# node.net
KiCad netlist of a schematic drawn in EAGLE
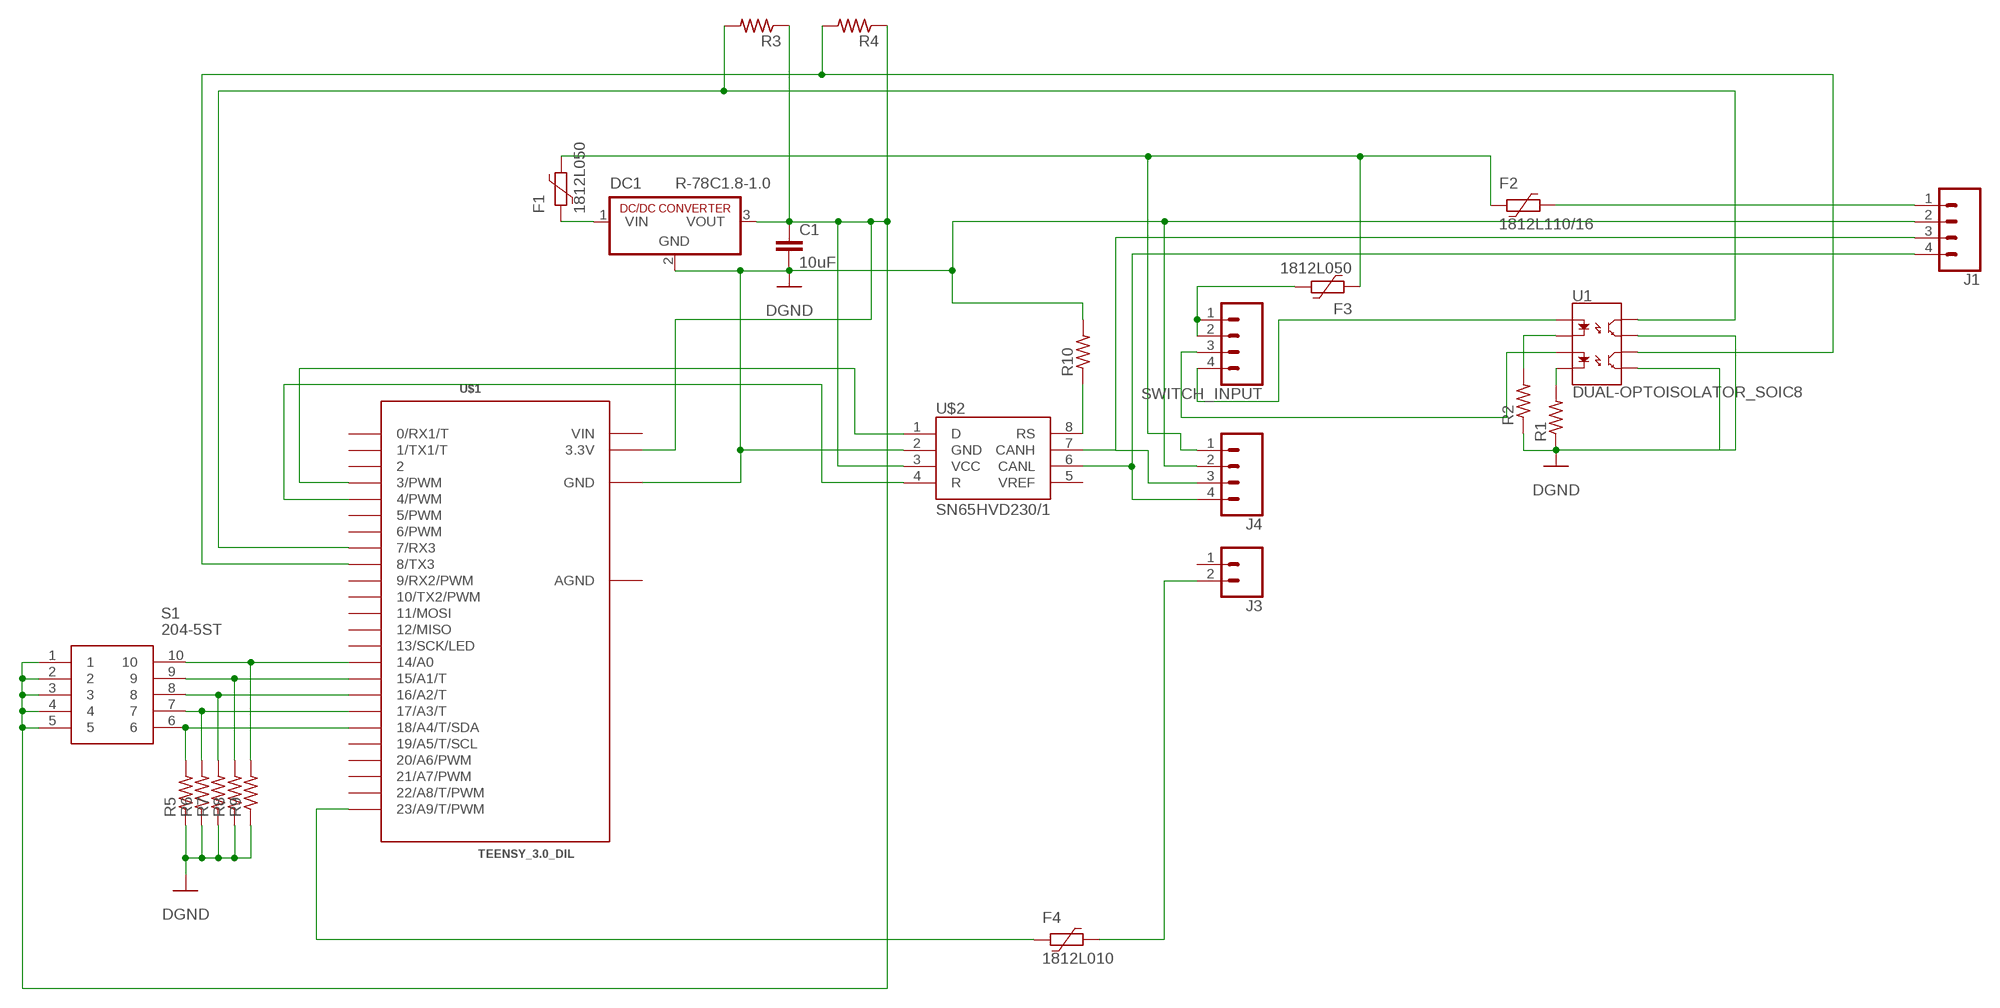
[diagram p0: schematic, sheet 1]

(export (version "E")
  (design (tool "Eeschema 10.0.6"))
  (components
    (comp (ref "C1")
      (value "10uF")
      (footprint "eagle-import:1206")
      (libsource (lib "eagle-import") (part "10UF-1206-6.3V-20%"))
    )
    (comp (ref "DC1")
      (value "R-78C1.8-1.0")
      (footprint "eagle-import:SIP3")
      (libsource (lib "eagle-import") (part "R-78C-1.01.8"))
    )
    (comp (ref "F1")
      (value "1812L050")
      (footprint "eagle-import:1812L")
      (fields (field (name "MF") "Littelfuse"))
      (libsource (lib "eagle-import") (part "?1812L050"))
    )
    (comp (ref "F2")
      (value "1812L110/16")
      (footprint "eagle-import:1812L")
      (fields (field (name "MF") "Littelfuse"))
      (libsource (lib "eagle-import") (part "?1812L110/16"))
    )
    (comp (ref "F3")
      (value "1812L050")
      (footprint "eagle-import:1812L")
      (fields (field (name "MF") "Littelfuse"))
      (libsource (lib "eagle-import") (part "?1812L050"))
    )
    (comp (ref "F4")
      (value "1812L010")
      (footprint "eagle-import:1812L")
      (fields (field (name "MF") "Littelfuse"))
      (libsource (lib "eagle-import") (part "?1812L010"))
    )
    (comp (ref "J1")
      (value "CONN_04POLAR")
      (footprint "eagle-import:MOLEX-1X4")
      (libsource (lib "eagle-import") (part "CONN_04POLAR"))
    )
    (comp (ref "J3")
      (value "CONN_02POLAR")
      (footprint "eagle-import:MOLEX-1X2")
      (libsource (lib "eagle-import") (part "CONN_02POLAR"))
    )
    (comp (ref "J4")
      (value "CONN_04POLAR")
      (footprint "eagle-import:MOLEX-1X4")
      (libsource (lib "eagle-import") (part "CONN_04POLAR"))
    )
    (comp (ref "R1")
      (value "R-US_R1206")
      (footprint "eagle-import:R1206")
      (libsource (lib "eagle-import") (part "R-US_R1206"))
    )
    (comp (ref "R2")
      (value "R-US_R1206")
      (footprint "eagle-import:R1206")
      (libsource (lib "eagle-import") (part "R-US_R1206"))
    )
    (comp (ref "R3")
      (value "R-US_R1206")
      (footprint "eagle-import:R1206")
      (libsource (lib "eagle-import") (part "R-US_R1206"))
    )
    (comp (ref "R4")
      (value "R-US_R1206")
      (footprint "eagle-import:R1206")
      (libsource (lib "eagle-import") (part "R-US_R1206"))
    )
    (comp (ref "R5")
      (value "R-US_R1206")
      (footprint "eagle-import:R1206")
      (libsource (lib "eagle-import") (part "R-US_R1206"))
    )
    (comp (ref "R6")
      (value "R-US_R1206")
      (footprint "eagle-import:R1206")
      (libsource (lib "eagle-import") (part "R-US_R1206"))
    )
    (comp (ref "R7")
      (value "R-US_R1206")
      (footprint "eagle-import:R1206")
      (libsource (lib "eagle-import") (part "R-US_R1206"))
    )
    (comp (ref "R8")
      (value "R-US_R1206")
      (footprint "eagle-import:R1206")
      (libsource (lib "eagle-import") (part "R-US_R1206"))
    )
    (comp (ref "R9")
      (value "R-US_R1206")
      (footprint "eagle-import:R1206")
      (libsource (lib "eagle-import") (part "R-US_R1206"))
    )
    (comp (ref "R10")
      (value "R-US_R1206")
      (footprint "eagle-import:R1206")
      (libsource (lib "eagle-import") (part "R-US_R1206"))
    )
    (comp (ref "S1")
      (value "204-5ST")
      (footprint "eagle-import:SOP254P1152X760-10N")
      (libsource (lib "eagle-import") (part "204-5ST"))
    )
    (comp (ref "SWITCH_INPUT")
      (value "CONN_04POLAR")
      (footprint "eagle-import:MOLEX-1X4")
      (libsource (lib "eagle-import") (part "CONN_04POLAR"))
    )
    (comp (ref "U$1")
      (value "TEENSY_3.0_DIL")
      (footprint "eagle-import:TEENSY_3.0-3.2&LC_DIL")
      (libsource (lib "eagle-import") (part "TEENSY_3.0_DIL"))
    )
    (comp (ref "U$2")
      (value "SN65HVD230/1")
      (footprint "eagle-import:SO8")
      (libsource (lib "eagle-import") (part "SN65HVD230/1"))
    )
    (comp (ref "U1")
      (value "DUAL-OPTOISOLATOR_SOIC8")
      (footprint "eagle-import:SO08")
      (libsource (lib "eagle-import") (part "DUAL-OPTOISOLATOR_SOIC8"))
    )
  )
  (nets
    (net (code "1") (name "/AGND") (class "Default")
      (node (ref "U$1") (pin "AGND") (pinfunction "AGND_AGND") (pintype "power_in"))
    )
    (net (code "2") (name "/VIN") (class "Default")
      (node (ref "U$1") (pin "VIN") (pinfunction "VIN_VIN") (pintype "power_in"))
    )
    (net (code "3") (name "DGND") (class "Default")
      (node (ref "C1") (pin "2") (pinfunction "2_2") (pintype "passive"))
      (node (ref "DC1") (pin "2") (pinfunction "GND_2") (pintype "passive"))
      (node (ref "J1") (pin "2") (pinfunction "2_2") (pintype "passive"))
      (node (ref "J4") (pin "2") (pinfunction "2_2") (pintype "passive"))
      (node (ref "R1") (pin "1") (pinfunction "1_1") (pintype "passive"))
      (node (ref "R10") (pin "2") (pinfunction "2_2") (pintype "passive"))
      (node (ref "R2") (pin "1") (pinfunction "1_1") (pintype "passive"))
      (node (ref "R5") (pin "1") (pinfunction "1_1") (pintype "passive"))
      (node (ref "R6") (pin "1") (pinfunction "1_1") (pintype "passive"))
      (node (ref "R7") (pin "1") (pinfunction "1_1") (pintype "passive"))
      (node (ref "R8") (pin "1") (pinfunction "1_1") (pintype "passive"))
      (node (ref "R9") (pin "1") (pinfunction "1_1") (pintype "passive"))
      (node (ref "U$1") (pin "GND") (pinfunction "GND_GND") (pintype "power_in"))
      (node (ref "U$2") (pin "2") (pinfunction "GND_2") (pintype "power_in"))
      (node (ref "U1") (pin "5") (pinfunction "EM2_5") (pintype "bidirectional"))
      (node (ref "U1") (pin "7") (pinfunction "EM1_7") (pintype "bidirectional"))
    )
    (net (code "4") (name "Net-(DC1-VIN)") (class "Default")
      (node (ref "DC1") (pin "1") (pinfunction "VIN_1") (pintype "passive"))
      (node (ref "F1") (pin "2") (pinfunction "2_2") (pintype "passive"))
    )
    (net (code "5") (name "Net-(DC1-VOUT)") (class "Default")
      (node (ref "C1") (pin "1") (pinfunction "1_1") (pintype "passive"))
      (node (ref "DC1") (pin "3") (pinfunction "VOUT_3") (pintype "passive"))
      (node (ref "R3") (pin "1") (pinfunction "1_1") (pintype "passive"))
      (node (ref "R4") (pin "1") (pinfunction "1_1") (pintype "passive"))
      (node (ref "S1") (pin "1") (pinfunction "1_1") (pintype "input"))
      (node (ref "S1") (pin "2") (pinfunction "2_2") (pintype "input"))
      (node (ref "S1") (pin "3") (pinfunction "3_3") (pintype "input"))
      (node (ref "S1") (pin "4") (pinfunction "4_4") (pintype "input"))
      (node (ref "S1") (pin "5") (pinfunction "5_5") (pintype "input"))
      (node (ref "U$1") (pin "3.3V") (pinfunction "3.3V_3.3V") (pintype "power_in"))
      (node (ref "U$2") (pin "3") (pinfunction "VCC_3") (pintype "power_in"))
    )
    (net (code "6") (name "Net-(F1-Pad1)") (class "Default")
      (node (ref "F1") (pin "1") (pinfunction "1_1") (pintype "passive"))
      (node (ref "F2") (pin "2") (pinfunction "2_2") (pintype "passive"))
      (node (ref "F3") (pin "2") (pinfunction "2_2") (pintype "passive"))
      (node (ref "J4") (pin "1") (pinfunction "1_1") (pintype "passive"))
    )
    (net (code "7") (name "Net-(F2-Pad1)") (class "Default")
      (node (ref "F2") (pin "1") (pinfunction "1_1") (pintype "passive"))
      (node (ref "J1") (pin "1") (pinfunction "1_1") (pintype "passive"))
    )
    (net (code "8") (name "Net-(F3-Pad1)") (class "Default")
      (node (ref "F3") (pin "1") (pinfunction "1_1") (pintype "passive"))
      (node (ref "SWITCH_INPUT") (pin "1") (pinfunction "1_1") (pintype "passive"))
      (node (ref "SWITCH_INPUT") (pin "2") (pinfunction "2_2") (pintype "passive"))
    )
    (net (code "9") (name "Net-(F4-Pad1)") (class "Default")
      (node (ref "F4") (pin "1") (pinfunction "1_1") (pintype "passive"))
      (node (ref "J3") (pin "2") (pinfunction "2_2") (pintype "passive"))
    )
    (net (code "10") (name "Net-(R9-Pad2)") (class "Default")
      (node (ref "R9") (pin "2") (pinfunction "2_2") (pintype "passive"))
      (node (ref "S1") (pin "10") (pinfunction "10_10") (pintype "output"))
      (node (ref "U$1") (pin "14/A0") (pinfunction "14/A0_14/A0") (pintype "bidirectional"))
    )
    (net (code "11") (name "Net-(U$1-3{slash}PWM)") (class "Default")
      (node (ref "U$1") (pin "3") (pinfunction "3/PWM_3") (pintype "bidirectional"))
      (node (ref "U$2") (pin "1") (pinfunction "D_1") (pintype "bidirectional"))
    )
    (net (code "12") (name "Net-(U$1-4{slash}PWM)") (class "Default")
      (node (ref "U$1") (pin "4") (pinfunction "4/PWM_4") (pintype "bidirectional"))
      (node (ref "U$2") (pin "4") (pinfunction "R_4") (pintype "bidirectional"))
    )
    (net (code "13") (name "Net-(U$1-7{slash}RX3)") (class "Default")
      (node (ref "R3") (pin "2") (pinfunction "2_2") (pintype "passive"))
      (node (ref "U$1") (pin "7") (pinfunction "7/RX3_7") (pintype "bidirectional"))
      (node (ref "U1") (pin "8") (pinfunction "CL1_8") (pintype "bidirectional"))
    )
    (net (code "14") (name "Net-(U$1-8{slash}TX3)") (class "Default")
      (node (ref "R4") (pin "2") (pinfunction "2_2") (pintype "passive"))
      (node (ref "U$1") (pin "8") (pinfunction "8/TX3_8") (pintype "bidirectional"))
      (node (ref "U1") (pin "6") (pinfunction "CL2_6") (pintype "bidirectional"))
    )
    (net (code "15") (name "Net-(U$1-15{slash}A1{slash}T)") (class "Default")
      (node (ref "R8") (pin "2") (pinfunction "2_2") (pintype "passive"))
      (node (ref "S1") (pin "9") (pinfunction "9_9") (pintype "output"))
      (node (ref "U$1") (pin "15/A1") (pinfunction "15/A1/T_15/A1") (pintype "bidirectional"))
    )
    (net (code "16") (name "Net-(U$1-16{slash}A2{slash}T)") (class "Default")
      (node (ref "R7") (pin "2") (pinfunction "2_2") (pintype "passive"))
      (node (ref "S1") (pin "8") (pinfunction "8_8") (pintype "output"))
      (node (ref "U$1") (pin "16/A2") (pinfunction "16/A2/T_16/A2") (pintype "bidirectional"))
    )
    (net (code "17") (name "Net-(U$1-17{slash}A3{slash}T)") (class "Default")
      (node (ref "R6") (pin "2") (pinfunction "2_2") (pintype "passive"))
      (node (ref "S1") (pin "7") (pinfunction "7_7") (pintype "output"))
      (node (ref "U$1") (pin "17/A3") (pinfunction "17/A3/T_17/A3") (pintype "bidirectional"))
    )
    (net (code "18") (name "Net-(U$1-18{slash}A4{slash}T{slash}SDA)") (class "Default")
      (node (ref "R5") (pin "2") (pinfunction "2_2") (pintype "passive"))
      (node (ref "S1") (pin "6") (pinfunction "6_6") (pintype "output"))
      (node (ref "U$1") (pin "18/A4") (pinfunction "18/A4/T/SDA_18/A4") (pintype "bidirectional"))
    )
    (net (code "19") (name "Net-(U$1-23{slash}A9{slash}T{slash}PWM)") (class "Default")
      (node (ref "F4") (pin "2") (pinfunction "2_2") (pintype "passive"))
      (node (ref "U$1") (pin "23/A9") (pinfunction "23/A9/T/PWM_23/A9") (pintype "bidirectional"))
    )
    (net (code "20") (name "Net-(U$2-CANH)") (class "Default")
      (node (ref "J1") (pin "3") (pinfunction "3_3") (pintype "passive"))
      (node (ref "J4") (pin "3") (pinfunction "3_3") (pintype "passive"))
      (node (ref "U$2") (pin "7") (pinfunction "CANH_7") (pintype "bidirectional"))
    )
    (net (code "21") (name "Net-(U$2-CANL)") (class "Default")
      (node (ref "J1") (pin "4") (pinfunction "4_4") (pintype "passive"))
      (node (ref "J4") (pin "4") (pinfunction "4_4") (pintype "passive"))
      (node (ref "U$2") (pin "6") (pinfunction "CANL_6") (pintype "bidirectional"))
    )
    (net (code "22") (name "Net-(U$2-RS)") (class "Default")
      (node (ref "R10") (pin "1") (pinfunction "1_1") (pintype "passive"))
      (node (ref "U$2") (pin "8") (pinfunction "RS_8") (pintype "bidirectional"))
    )
    (net (code "23") (name "Net-(U1-A1)") (class "Default")
      (node (ref "SWITCH_INPUT") (pin "4") (pinfunction "4_4") (pintype "passive"))
      (node (ref "U1") (pin "1") (pinfunction "A1_1") (pintype "bidirectional"))
    )
    (net (code "24") (name "Net-(U1-A2)") (class "Default")
      (node (ref "SWITCH_INPUT") (pin "3") (pinfunction "3_3") (pintype "passive"))
      (node (ref "U1") (pin "3") (pinfunction "A2_3") (pintype "bidirectional"))
    )
    (net (code "25") (name "Net-(U1-C1)") (class "Default")
      (node (ref "R2") (pin "2") (pinfunction "2_2") (pintype "passive"))
      (node (ref "U1") (pin "2") (pinfunction "C1_2") (pintype "bidirectional"))
    )
    (net (code "26") (name "Net-(U1-C2)") (class "Default")
      (node (ref "R1") (pin "2") (pinfunction "2_2") (pintype "passive"))
      (node (ref "U1") (pin "4") (pinfunction "C2_4") (pintype "bidirectional"))
    )
    (net (code "27") (name "unconnected-(J3-Pad1)") (class "Default")
      (node (ref "J3") (pin "1") (pinfunction "1_1") (pintype "passive"))
    )
    (net (code "28") (name "unconnected-(U$1-0{slash}RX1{slash}T-Pad0)") (class "Default")
      (node (ref "U$1") (pin "0") (pinfunction "0/RX1/T_0") (pintype "bidirectional"))
    )
    (net (code "29") (name "unconnected-(U$1-1{slash}TX1{slash}T-Pad1)") (class "Default")
      (node (ref "U$1") (pin "1") (pinfunction "1/TX1/T_1") (pintype "bidirectional"))
    )
    (net (code "30") (name "unconnected-(U$1-5{slash}PWM-Pad5)") (class "Default")
      (node (ref "U$1") (pin "5") (pinfunction "5/PWM_5") (pintype "bidirectional"))
    )
    (net (code "31") (name "unconnected-(U$1-6{slash}PWM-Pad6)") (class "Default")
      (node (ref "U$1") (pin "6") (pinfunction "6/PWM_6") (pintype "bidirectional"))
    )
    (net (code "32") (name "unconnected-(U$1-9{slash}RX2{slash}PWM-Pad9)") (class "Default")
      (node (ref "U$1") (pin "9") (pinfunction "9/RX2/PWM_9") (pintype "bidirectional"))
    )
    (net (code "33") (name "unconnected-(U$1-10{slash}TX2{slash}PWM-Pad10)") (class "Default")
      (node (ref "U$1") (pin "10") (pinfunction "10/TX2/PWM_10") (pintype "bidirectional"))
    )
    (net (code "34") (name "unconnected-(U$1-11{slash}MOSI-Pad11)") (class "Default")
      (node (ref "U$1") (pin "11") (pinfunction "11/MOSI_11") (pintype "bidirectional"))
    )
    (net (code "35") (name "unconnected-(U$1-12{slash}MISO-Pad12)") (class "Default")
      (node (ref "U$1") (pin "12") (pinfunction "12/MISO_12") (pintype "bidirectional"))
    )
    (net (code "36") (name "unconnected-(U$1-13{slash}SCK{slash}LED-Pad13)") (class "Default")
      (node (ref "U$1") (pin "13") (pinfunction "13/SCK/LED_13") (pintype "bidirectional"))
    )
    (net (code "37") (name "unconnected-(U$1-19{slash}A5{slash}T{slash}SCL-Pad19{slash}A5)") (class "Default")
      (node (ref "U$1") (pin "19/A5") (pinfunction "19/A5/T/SCL_19/A5") (pintype "bidirectional"))
    )
    (net (code "38") (name "unconnected-(U$1-20{slash}A6{slash}PWM-Pad20{slash}A6)") (class "Default")
      (node (ref "U$1") (pin "20/A6") (pinfunction "20/A6/PWM_20/A6") (pintype "bidirectional"))
    )
    (net (code "39") (name "unconnected-(U$1-21{slash}A7{slash}PWM-Pad21{slash}A7)") (class "Default")
      (node (ref "U$1") (pin "21/A7") (pinfunction "21/A7/PWM_21/A7") (pintype "bidirectional"))
    )
    (net (code "40") (name "unconnected-(U$1-22{slash}A8{slash}T{slash}PWM-Pad22{slash}A8)") (class "Default")
      (node (ref "U$1") (pin "22/A8") (pinfunction "22/A8/T/PWM_22/A8") (pintype "bidirectional"))
    )
    (net (code "41") (name "unconnected-(U$1-Pad2)") (class "Default")
      (node (ref "U$1") (pin "2") (pinfunction "2_2") (pintype "bidirectional"))
    )
    (net (code "42") (name "unconnected-(U$2-VREF-Pad5)") (class "Default")
      (node (ref "U$2") (pin "5") (pinfunction "VREF_5") (pintype "bidirectional"))
    )
  )
)
